# STRWL-S01-V01-Master1.net
KiCad netlist of a schematic drawn in Altium Designer
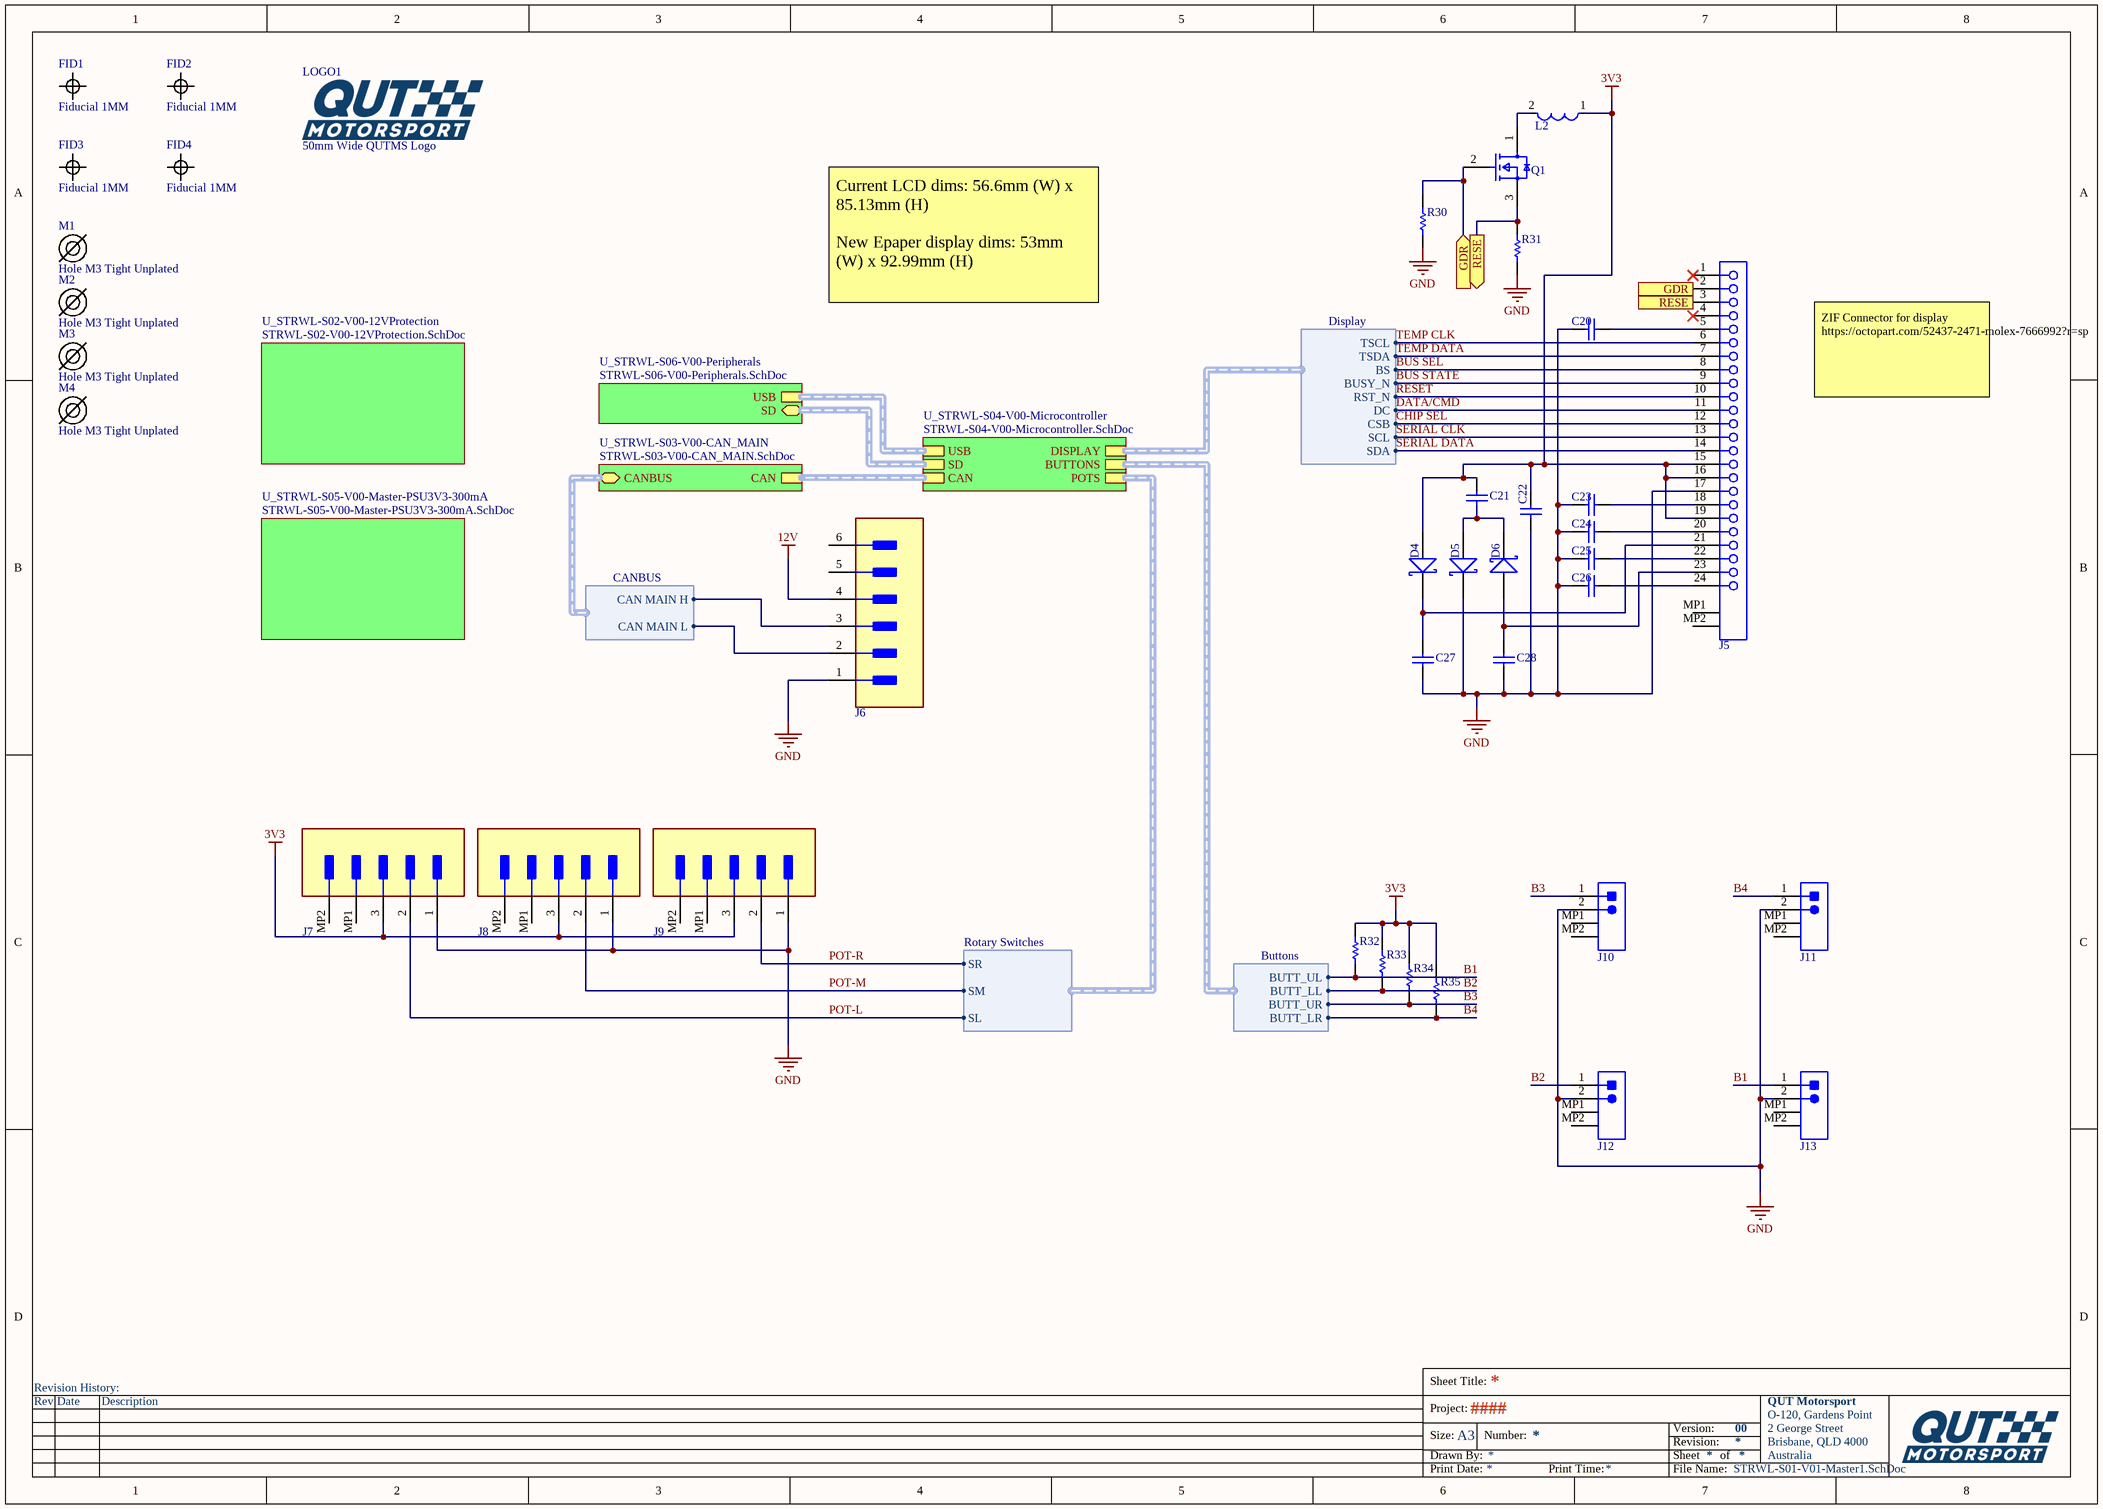
[diagram p0: STRWL-S01-V01-Master1.SchDoc]

(export (version "E")
  (design (tool "Eeschema 10.0.6"))
  (components
    (comp (ref "C20")
      (value "1uF 25V 5% X7R 0603")
      (footprint "Cap_Ceramic_0603")
      (description "Capacitor, Ceramic, SMD, 1uF, 25V, 5%, X7R, 0603")
      (libsource (lib "StandardCapacitors") (part "1uF 25V 5% X7R 0603"))
    )
    (comp (ref "C21")
      (value "4u7 50V 5% X7R 0603")
      (footprint "Cap_Ceramic_0603")
      (description "Capacitor, Ceramic, SMD, 4u7, 50V, 5%, X7R, 0603")
      (libsource (lib "StandardCapacitors") (part "4u7 50V 5% X7R 0603"))
    )
    (comp (ref "C22")
      (value "1uF 25V 5% X7R 0603")
      (footprint "Cap_Ceramic_0603")
      (description "Capacitor, Ceramic, SMD, 1uF, 25V, 5%, X7R, 0603")
      (libsource (lib "StandardCapacitors") (part "1uF 25V 5% X7R 0603"))
    )
    (comp (ref "C23")
      (value "1uF 25V 5% X7R 0603")
      (footprint "Cap_Ceramic_0603")
      (description "Capacitor, Ceramic, SMD, 1uF, 25V, 5%, X7R, 0603")
      (libsource (lib "StandardCapacitors") (part "1uF 25V 5% X7R 0603"))
    )
    (comp (ref "C24")
      (value "1uF 25V 5% X7R 0603")
      (footprint "Cap_Ceramic_0603")
      (description "Capacitor, Ceramic, SMD, 1uF, 25V, 5%, X7R, 0603")
      (libsource (lib "StandardCapacitors") (part "1uF 25V 5% X7R 0603"))
    )
    (comp (ref "C25")
      (value "1uF 25V 5% X7R 0603")
      (footprint "Cap_Ceramic_0603")
      (description "Capacitor, Ceramic, SMD, 1uF, 25V, 5%, X7R, 0603")
      (libsource (lib "StandardCapacitors") (part "1uF 25V 5% X7R 0603"))
    )
    (comp (ref "C26")
      (value "1uF 25V 5% X7R 0603")
      (footprint "Cap_Ceramic_0603")
      (description "Capacitor, Ceramic, SMD, 1uF, 25V, 5%, X7R, 0603")
      (libsource (lib "StandardCapacitors") (part "1uF 25V 5% X7R 0603"))
    )
    (comp (ref "C27")
      (value "1uF 25V 5% X7R 0603")
      (footprint "Cap_Ceramic_0603")
      (description "Capacitor, Ceramic, SMD, 1uF, 25V, 5%, X7R, 0603")
      (libsource (lib "StandardCapacitors") (part "1uF 25V 5% X7R 0603"))
    )
    (comp (ref "C28")
      (value "1uF 25V 5% X7R 0603")
      (footprint "Cap_Ceramic_0603")
      (description "Capacitor, Ceramic, SMD, 1uF, 25V, 5%, X7R, 0603")
      (libsource (lib "StandardCapacitors") (part "1uF 25V 5% X7R 0603"))
    )
    (comp (ref "D4")
      (value "STPS0530Z")
      (footprint "SOD123")
      (description "Diode, Schottky Barrier Rectifier, 30 V, 0.5 A, STPS0530Z")
      (libsource (lib "QUTMS_DiodeLibrary") (part "STPS0530Z"))
    )
    (comp (ref "D5")
      (value "STPS0530Z")
      (footprint "SOD123")
      (description "Diode, Schottky Barrier Rectifier, 30 V, 0.5 A, STPS0530Z")
      (libsource (lib "QUTMS_DiodeLibrary") (part "STPS0530Z"))
    )
    (comp (ref "D6")
      (value "STPS0530Z")
      (footprint "SOD123")
      (description "Diode, Schottky Barrier Rectifier, 30 V, 0.5 A, STPS0530Z")
      (libsource (lib "QUTMS_DiodeLibrary") (part "STPS0530Z"))
    )
    (comp (ref "FID1")
      (value "Fiducial 1MM")
      (footprint "FIDUCIAL 1MM")
      (libsource (lib "QUTMS-MCISOLibrary") (part "Fiducial 1MM"))
    )
    (comp (ref "FID2")
      (value "Fiducial 1MM")
      (footprint "FIDUCIAL 1MM")
      (libsource (lib "QUTMS-MCISOLibrary") (part "Fiducial 1MM"))
    )
    (comp (ref "FID3")
      (value "Fiducial 1MM")
      (footprint "FIDUCIAL 1MM")
      (libsource (lib "QUTMS-MCISOLibrary") (part "Fiducial 1MM"))
    )
    (comp (ref "FID4")
      (value "Fiducial 1MM")
      (footprint "FIDUCIAL 1MM")
      (libsource (lib "QUTMS-MCISOLibrary") (part "Fiducial 1MM"))
    )
    (comp (ref "J5")
      (value "52437-2471")
      (footprint "MOLX-52437-2471")
      (fields (field (name "MANUFACTURER") "Molex"))
      (libsource (lib "Molex_52437_2471") (part "52437-2471"))
    )
    (comp (ref "J6")
      (value "JST PH 4 Way SMD Header")
      (footprint "JST 4P SMD")
      (libsource (lib "QUTMS_JSTHeaderLibrary") (part "JST PH 4 Way SMD Header"))
    )
    (comp (ref "J7")
      (value "JST PH 3 Way SMD Header")
      (footprint "JST 3P SMD")
      (libsource (lib "QUTMS_JSTHeaderLibrary") (part "JST PH 3 Way SMD Header"))
    )
    (comp (ref "J8")
      (value "JST PH 3 Way SMD Header")
      (footprint "JST 3P SMD")
      (libsource (lib "QUTMS_JSTHeaderLibrary") (part "JST PH 3 Way SMD Header"))
    )
    (comp (ref "J9")
      (value "JST PH 3 Way SMD Header")
      (footprint "JST 3P SMD")
      (libsource (lib "QUTMS_JSTHeaderLibrary") (part "JST PH 3 Way SMD Header"))
    )
    (comp (ref "J10")
      (value "JST PH 2 Way SMD Header")
      (footprint "JST 2P SMD")
      (fields (field (name "PARTNUMBER") "S2B-PH-SM4-TB(LF)(SN)"))
      (libsource (lib "QUTMS_JSTHeaderLibrary") (part "JST PH 2 Way SMD Header"))
    )
    (comp (ref "J11")
      (value "JST PH 2 Way SMD Header")
      (footprint "JST 2P SMD")
      (fields (field (name "PARTNUMBER") "S2B-PH-SM4-TB(LF)(SN)"))
      (libsource (lib "QUTMS_JSTHeaderLibrary") (part "JST PH 2 Way SMD Header"))
    )
    (comp (ref "J12")
      (value "JST PH 2 Way SMD Header")
      (footprint "JST 2P SMD")
      (fields (field (name "PARTNUMBER") "S2B-PH-SM4-TB(LF)(SN)"))
      (libsource (lib "QUTMS_JSTHeaderLibrary") (part "JST PH 2 Way SMD Header"))
    )
    (comp (ref "J13")
      (value "JST PH 2 Way SMD Header")
      (footprint "JST 2P SMD")
      (fields (field (name "PARTNUMBER") "S2B-PH-SM4-TB(LF)(SN)"))
      (libsource (lib "QUTMS_JSTHeaderLibrary") (part "JST PH 2 Way SMD Header"))
    )
    (comp (ref "L2")
      (value "LQM21FN100M70L")
      (footprint "Murata_LQM21FN_70_IPC_C")
      (libsource (lib "QUTMS_InductorLibrary") (part "LQM21FN100M70L"))
    )
    (comp (ref "LOGO1")
      (value "50mm Wide QUTMS Logo")
      (footprint "QUTMS LOGO 50MM")
      (libsource (lib "QUTMS-MCISOLibrary") (part "QUTMS Logo 50mm"))
    )
    (comp (ref "M1")
      (value "Hole M3 Tight Unplated")
      (footprint "M3.2 UNPLATED")
      (description "M3.2 Hole, No Plating")
      (libsource (lib "QUTMS-MCISOLibrary") (part "Hole M3 Tight Unplated"))
    )
    (comp (ref "M2")
      (value "Hole M3 Tight Unplated")
      (footprint "M3.2 UNPLATED")
      (description "M3.2 Hole, No Plating")
      (libsource (lib "QUTMS-MCISOLibrary") (part "Hole M3 Tight Unplated"))
    )
    (comp (ref "M3")
      (value "Hole M3 Tight Unplated")
      (footprint "M3.2 UNPLATED")
      (description "M3.2 Hole, No Plating")
      (libsource (lib "QUTMS-MCISOLibrary") (part "Hole M3 Tight Unplated"))
    )
    (comp (ref "M4")
      (value "Hole M3 Tight Unplated")
      (footprint "M3.2 UNPLATED")
      (description "M3.2 Hole, No Plating")
      (libsource (lib "QUTMS-MCISOLibrary") (part "Hole M3 Tight Unplated"))
    )
    (comp (ref "Q1")
      (value "MOSFET N-CH 30V 4A SOT323")
      (footprint "Diodes_SOT323_0")
      (description "N-Channel 30V 4A (Ta) 770mW (Ta) Surface Mount SOT-323")
      (libsource (lib "QUTMS_DiodeLibrary") (part "DMN3065LW-13"))
    )
    (comp (ref "R30")
      (value "10k 1% 0603")
      (footprint "Res_ThinFilm_0603")
      (description "Resistor, SMD, 10k, 0.1W, 1%, 0603")
      (libsource (lib "StandardResistors") (part "10k 1% 0603"))
    )
    (comp (ref "R31")
      (value "0R47 5% 0603")
      (footprint "Res_ThinFilm_0603")
      (description "Resistor, SMD, 0R, 0.1W, 5%, 0603")
      (libsource (lib "StandardResistors") (part "0R47 5% 0603_1"))
    )
    (comp (ref "R32")
      (value "10k 5% 0603")
      (footprint "Res_ThinFilm_0603")
      (description "Resistor, SMD, 10k, 0.1W, 5%, 0603")
      (libsource (lib "StandardResistors") (part "10k 5% 0603"))
    )
    (comp (ref "R33")
      (value "10k 5% 0603")
      (footprint "Res_ThinFilm_0603")
      (description "Resistor, SMD, 10k, 0.1W, 5%, 0603")
      (libsource (lib "StandardResistors") (part "10k 5% 0603"))
    )
    (comp (ref "R34")
      (value "10k 5% 0603")
      (footprint "Res_ThinFilm_0603")
      (description "Resistor, SMD, 10k, 0.1W, 5%, 0603")
      (libsource (lib "StandardResistors") (part "10k 5% 0603"))
    )
    (comp (ref "R35")
      (value "10k 5% 0603")
      (footprint "Res_ThinFilm_0603")
      (description "Resistor, SMD, 10k, 0.1W, 5%, 0603")
      (libsource (lib "StandardResistors") (part "10k 5% 0603"))
    )
  )
  (nets
    (net (code "6") (name "/B1") (class "Default")
      (node (ref "J13") (pin "1") (pinfunction "1_1") (pintype "passive"))
      (node (ref "R32") (pin "2") (pinfunction "2_2") (pintype "passive"))
    )
    (net (code "7") (name "/B2") (class "Default")
      (node (ref "J12") (pin "1") (pinfunction "1_1") (pintype "passive"))
      (node (ref "R33") (pin "2") (pinfunction "2_2") (pintype "passive"))
    )
    (net (code "8") (name "/B3") (class "Default")
      (node (ref "J10") (pin "1") (pinfunction "1_1") (pintype "passive"))
      (node (ref "R34") (pin "1") (pinfunction "1_1") (pintype "passive"))
    )
    (net (code "9") (name "/B4") (class "Default")
      (node (ref "J11") (pin "1") (pinfunction "1_1") (pintype "passive"))
      (node (ref "R35") (pin "1") (pinfunction "1_1") (pintype "passive"))
    )
    (net (code "10") (name "/BUS SEL") (class "Default")
      (node (ref "J5") (pin "8") (pinfunction "8_8") (pintype "passive"))
    )
    (net (code "11") (name "/BUS STATE") (class "Default")
      (node (ref "J5") (pin "9") (pinfunction "9_9") (pintype "passive"))
    )
    (net (code "12") (name "/CAN MAIN H") (class "Default")
      (node (ref "J6") (pin "3") (pinfunction "3_3") (pintype "passive"))
    )
    (net (code "13") (name "/CAN MAIN L") (class "Default")
      (node (ref "J6") (pin "2") (pinfunction "2_2") (pintype "passive"))
    )
    (net (code "15") (name "/CHIP SEL") (class "Default")
      (node (ref "J5") (pin "12") (pinfunction "12_12") (pintype "passive"))
    )
    (net (code "16") (name "/DATA{slash}CMD") (class "Default")
      (node (ref "J5") (pin "11") (pinfunction "11_11") (pintype "passive"))
    )
    (net (code "17") (name "/GDR") (class "Default")
      (node (ref "J5") (pin "2") (pinfunction "2_2") (pintype "passive"))
      (node (ref "Q1") (pin "2") (pinfunction "G_2") (pintype "passive"))
      (node (ref "R30") (pin "1") (pinfunction "1_1") (pintype "passive"))
    )
    (net (code "18") (name "/POT-L") (class "Default")
      (node (ref "J7") (pin "2") (pinfunction "2_2") (pintype "passive"))
    )
    (net (code "19") (name "/POT-M") (class "Default")
      (node (ref "J8") (pin "2") (pinfunction "2_2") (pintype "passive"))
    )
    (net (code "20") (name "/POT-R") (class "Default")
      (node (ref "J9") (pin "2") (pinfunction "2_2") (pintype "passive"))
    )
    (net (code "21") (name "/RESE") (class "Default")
      (node (ref "J5") (pin "3") (pinfunction "3_3") (pintype "passive"))
      (node (ref "Q1") (pin "3") (pinfunction "S_3") (pintype "passive"))
      (node (ref "R31") (pin "2") (pinfunction "2_2") (pintype "passive"))
    )
    (net (code "22") (name "/RESET") (class "Default")
      (node (ref "J5") (pin "10") (pinfunction "10_10") (pintype "passive"))
    )
    (net (code "24") (name "/SERIAL CLK") (class "Default")
      (node (ref "J5") (pin "13") (pinfunction "13_13") (pintype "passive"))
    )
    (net (code "25") (name "/SERIAL DATA") (class "Default")
      (node (ref "J5") (pin "14") (pinfunction "14_14") (pintype "passive"))
    )
    (net (code "26") (name "/TEMP CLK") (class "Default")
      (node (ref "J5") (pin "6") (pinfunction "6_6") (pintype "passive"))
    )
    (net (code "27") (name "/TEMP DATA") (class "Default")
      (node (ref "J5") (pin "7") (pinfunction "7_7") (pintype "passive"))
    )
    (net (code "33") (name "3V3") (class "Default")
      (node (ref "C21") (pin "2") (pinfunction "2_2") (pintype "passive"))
      (node (ref "C22") (pin "2") (pinfunction "2_2") (pintype "passive"))
      (node (ref "D4") (pin "A") (pinfunction "A_A") (pintype "passive"))
      (node (ref "J5") (pin "15") (pinfunction "15_15") (pintype "passive"))
      (node (ref "J5") (pin "16") (pinfunction "16_16") (pintype "passive"))
      (node (ref "J5") (pin "19") (pinfunction "19_19") (pintype "passive"))
      (node (ref "J7") (pin "3") (pinfunction "3_3") (pintype "passive"))
      (node (ref "J8") (pin "3") (pinfunction "3_3") (pintype "passive"))
      (node (ref "J9") (pin "3") (pinfunction "3_3") (pintype "passive"))
      (node (ref "L2") (pin "1") (pinfunction "1_1") (pintype "passive"))
      (node (ref "R32") (pin "1") (pinfunction "1_1") (pintype "passive"))
      (node (ref "R33") (pin "1") (pinfunction "1_1") (pintype "passive"))
      (node (ref "R34") (pin "2") (pinfunction "2_2") (pintype "passive"))
      (node (ref "R35") (pin "2") (pinfunction "2_2") (pintype "passive"))
    )
    (net (code "34") (name "12V") (class "Default")
      (node (ref "J6") (pin "4") (pinfunction "4_4") (pintype "passive"))
    )
    (net (code "35") (name "GND") (class "Default")
      (node (ref "C20") (pin "1") (pinfunction "1_1") (pintype "passive"))
      (node (ref "C22") (pin "1") (pinfunction "1_1") (pintype "passive"))
      (node (ref "C23") (pin "1") (pinfunction "1_1") (pintype "passive"))
      (node (ref "C24") (pin "1") (pinfunction "1_1") (pintype "passive"))
      (node (ref "C25") (pin "1") (pinfunction "1_1") (pintype "passive"))
      (node (ref "C26") (pin "1") (pinfunction "1_1") (pintype "passive"))
      (node (ref "C27") (pin "1") (pinfunction "1_1") (pintype "passive"))
      (node (ref "C28") (pin "1") (pinfunction "1_1") (pintype "passive"))
      (node (ref "D5") (pin "K") (pinfunction "K_K") (pintype "passive"))
      (node (ref "J10") (pin "2") (pinfunction "2_2") (pintype "passive"))
      (node (ref "J11") (pin "2") (pinfunction "2_2") (pintype "passive"))
      (node (ref "J12") (pin "2") (pinfunction "2_2") (pintype "passive"))
      (node (ref "J13") (pin "2") (pinfunction "2_2") (pintype "passive"))
      (node (ref "J5") (pin "17") (pinfunction "17_17") (pintype "passive"))
      (node (ref "J6") (pin "1") (pinfunction "1_1") (pintype "passive"))
      (node (ref "J7") (pin "1") (pinfunction "1_1") (pintype "passive"))
      (node (ref "J8") (pin "1") (pinfunction "1_1") (pintype "passive"))
      (node (ref "J9") (pin "1") (pinfunction "1_1") (pintype "passive"))
      (node (ref "R30") (pin "2") (pinfunction "2_2") (pintype "passive"))
      (node (ref "R31") (pin "1") (pinfunction "1_1") (pintype "passive"))
    )
    (net (code "36") (name "Net-(C20-Pad2)") (class "Default")
      (node (ref "C20") (pin "2") (pinfunction "2_2") (pintype "passive"))
      (node (ref "J5") (pin "5") (pinfunction "5_5") (pintype "passive"))
    )
    (net (code "37") (name "Net-(C21-Pad1)") (class "Default")
      (node (ref "C21") (pin "1") (pinfunction "1_1") (pintype "passive"))
      (node (ref "D5") (pin "A") (pinfunction "A_A") (pintype "passive"))
      (node (ref "D6") (pin "K") (pinfunction "K_K") (pintype "passive"))
    )
    (net (code "38") (name "Net-(C23-Pad2)") (class "Default")
      (node (ref "C23") (pin "2") (pinfunction "2_2") (pintype "passive"))
      (node (ref "J5") (pin "18") (pinfunction "18_18") (pintype "passive"))
    )
    (net (code "39") (name "Net-(C24-Pad2)") (class "Default")
      (node (ref "C24") (pin "2") (pinfunction "2_2") (pintype "passive"))
      (node (ref "J5") (pin "20") (pinfunction "20_20") (pintype "passive"))
    )
    (net (code "40") (name "Net-(C25-Pad2)") (class "Default")
      (node (ref "C25") (pin "2") (pinfunction "2_2") (pintype "passive"))
      (node (ref "J5") (pin "22") (pinfunction "22_22") (pintype "passive"))
    )
    (net (code "41") (name "Net-(C26-Pad2)") (class "Default")
      (node (ref "C26") (pin "2") (pinfunction "2_2") (pintype "passive"))
      (node (ref "J5") (pin "24") (pinfunction "24_24") (pintype "passive"))
    )
    (net (code "42") (name "Net-(C27-Pad2)") (class "Default")
      (node (ref "C27") (pin "2") (pinfunction "2_2") (pintype "passive"))
      (node (ref "D4") (pin "K") (pinfunction "K_K") (pintype "passive"))
      (node (ref "J5") (pin "21") (pinfunction "21_21") (pintype "passive"))
    )
    (net (code "43") (name "Net-(C28-Pad2)") (class "Default")
      (node (ref "C28") (pin "2") (pinfunction "2_2") (pintype "passive"))
      (node (ref "D6") (pin "A") (pinfunction "A_A") (pintype "passive"))
      (node (ref "J5") (pin "23") (pinfunction "23_23") (pintype "passive"))
    )
    (net (code "44") (name "Net-(Q1-D)") (class "Default")
      (node (ref "L2") (pin "2") (pinfunction "2_2") (pintype "passive"))
      (node (ref "Q1") (pin "1") (pinfunction "D_1") (pintype "passive"))
    )
    (net (code "45") (name "unconnected-(J5-Pad1)") (class "Default")
      (node (ref "J5") (pin "1") (pinfunction "1_1") (pintype "passive+no_connect"))
    )
    (net (code "46") (name "unconnected-(J5-Pad4)") (class "Default")
      (node (ref "J5") (pin "4") (pinfunction "4_4") (pintype "passive+no_connect"))
    )
    (net (code "47") (name "unconnected-(J5-PadMP1)") (class "Default")
      (node (ref "J5") (pin "MP1") (pinfunction "MP1_MP1") (pintype "passive"))
    )
    (net (code "48") (name "unconnected-(J5-PadMP2)") (class "Default")
      (node (ref "J5") (pin "MP2") (pinfunction "MP2_MP2") (pintype "passive"))
    )
    (net (code "49") (name "unconnected-(J6-MNT_1-Pad5)") (class "Default")
      (node (ref "J6") (pin "5") (pinfunction "MNT_1_5") (pintype "passive"))
    )
    (net (code "50") (name "unconnected-(J6-MNT_2-Pad6)") (class "Default")
      (node (ref "J6") (pin "6") (pinfunction "MNT_2_6") (pintype "passive"))
    )
    (net (code "51") (name "unconnected-(J7-MNT_1-PadMP1)") (class "Default")
      (node (ref "J7") (pin "MP1") (pinfunction "MNT_1_MP1") (pintype "passive"))
    )
    (net (code "52") (name "unconnected-(J7-MNT_2-PadMP2)") (class "Default")
      (node (ref "J7") (pin "MP2") (pinfunction "MNT_2_MP2") (pintype "passive"))
    )
    (net (code "53") (name "unconnected-(J8-MNT_1-PadMP1)") (class "Default")
      (node (ref "J8") (pin "MP1") (pinfunction "MNT_1_MP1") (pintype "passive"))
    )
    (net (code "54") (name "unconnected-(J8-MNT_2-PadMP2)") (class "Default")
      (node (ref "J8") (pin "MP2") (pinfunction "MNT_2_MP2") (pintype "passive"))
    )
    (net (code "55") (name "unconnected-(J9-MNT_1-PadMP1)") (class "Default")
      (node (ref "J9") (pin "MP1") (pinfunction "MNT_1_MP1") (pintype "passive"))
    )
    (net (code "56") (name "unconnected-(J9-MNT_2-PadMP2)") (class "Default")
      (node (ref "J9") (pin "MP2") (pinfunction "MNT_2_MP2") (pintype "passive"))
    )
    (net (code "57") (name "unconnected-(J10-PadMP1)") (class "Default")
      (node (ref "J10") (pin "MP1") (pinfunction "MP1_MP1") (pintype "passive"))
    )
    (net (code "58") (name "unconnected-(J10-PadMP2)") (class "Default")
      (node (ref "J10") (pin "MP2") (pinfunction "MP2_MP2") (pintype "passive"))
    )
    (net (code "59") (name "unconnected-(J11-PadMP1)") (class "Default")
      (node (ref "J11") (pin "MP1") (pinfunction "MP1_MP1") (pintype "passive"))
    )
    (net (code "60") (name "unconnected-(J11-PadMP2)") (class "Default")
      (node (ref "J11") (pin "MP2") (pinfunction "MP2_MP2") (pintype "passive"))
    )
    (net (code "61") (name "unconnected-(J12-PadMP1)") (class "Default")
      (node (ref "J12") (pin "MP1") (pinfunction "MP1_MP1") (pintype "passive"))
    )
    (net (code "62") (name "unconnected-(J12-PadMP2)") (class "Default")
      (node (ref "J12") (pin "MP2") (pinfunction "MP2_MP2") (pintype "passive"))
    )
    (net (code "63") (name "unconnected-(J13-PadMP1)") (class "Default")
      (node (ref "J13") (pin "MP1") (pinfunction "MP1_MP1") (pintype "passive"))
    )
    (net (code "64") (name "unconnected-(J13-PadMP2)") (class "Default")
      (node (ref "J13") (pin "MP2") (pinfunction "MP2_MP2") (pintype "passive"))
    )
  )
)
